# maplemini.net
KiCad netlist of a schematic drawn in EAGLE
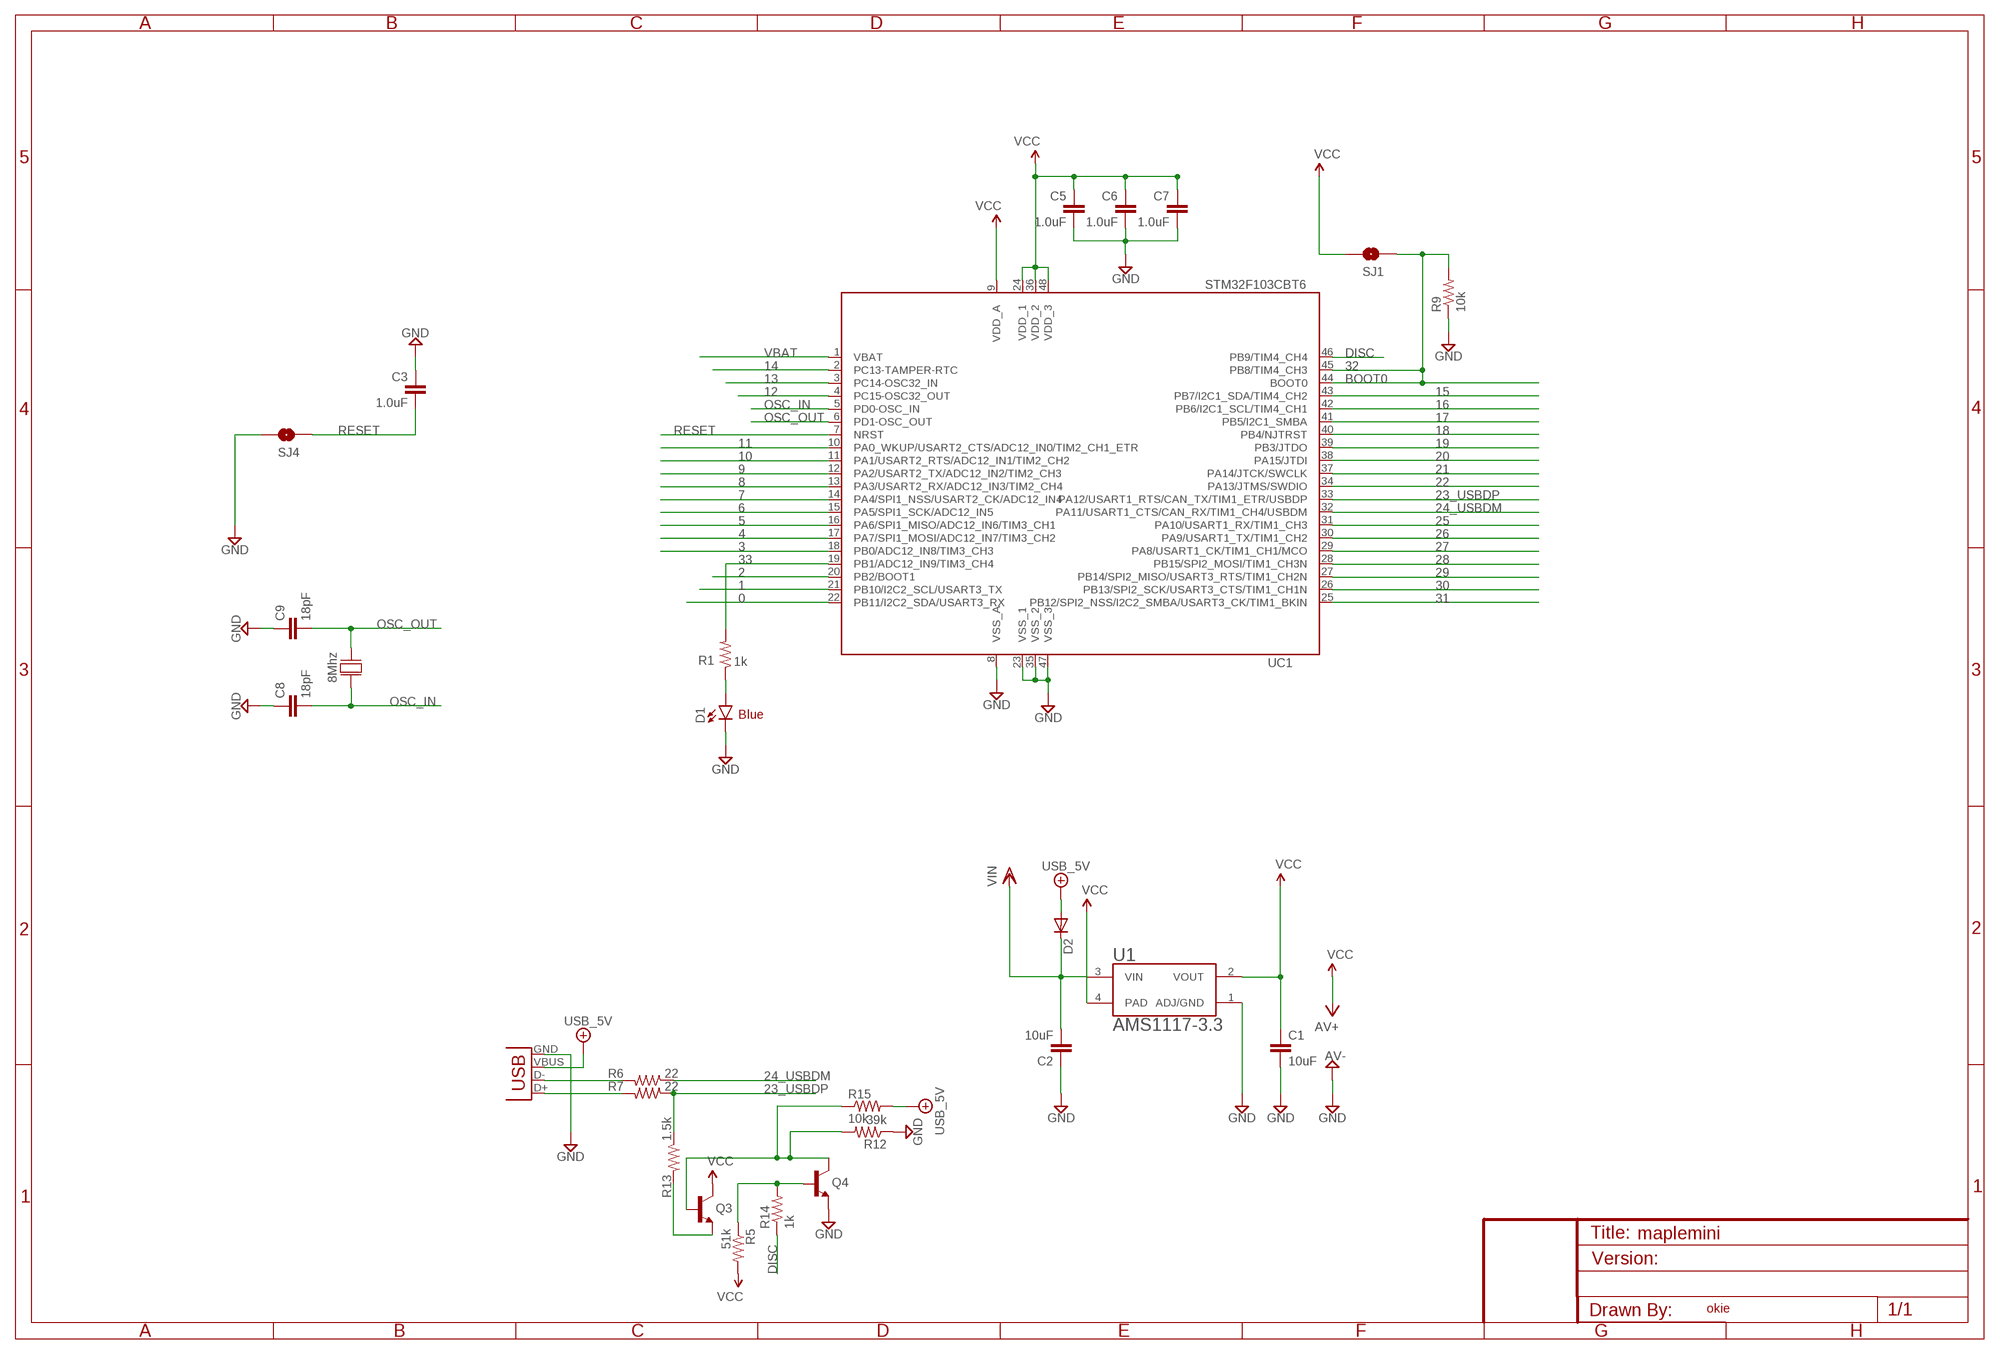
[diagram p0: schematic, sheet 1]

(export (version "E")
  (design (tool "Eeschema 10.0.6"))
  (components
    (comp (ref "C1")
      (value "10uF")
      (footprint "eagle-import:0805")
      (libsource (lib "eagle-import") (part "CAP0805"))
    )
    (comp (ref "C2")
      (value "10uF")
      (footprint "eagle-import:0805")
      (libsource (lib "eagle-import") (part "CAP0805"))
    )
    (comp (ref "C3")
      (value "1.0uF")
      (footprint "eagle-import:0603")
      (libsource (lib "eagle-import") (part "1.0UF-0603-16V-10%"))
    )
    (comp (ref "C5")
      (value "1.0uF")
      (footprint "eagle-import:0603")
      (libsource (lib "eagle-import") (part "1.0UF-0603-16V-10%"))
    )
    (comp (ref "C6")
      (value "1.0uF")
      (footprint "eagle-import:0603")
      (libsource (lib "eagle-import") (part "1.0UF-0603-16V-10%"))
    )
    (comp (ref "C7")
      (value "1.0uF")
      (footprint "eagle-import:0603")
      (libsource (lib "eagle-import") (part "1.0UF-0603-16V-10%"))
    )
    (comp (ref "C8")
      (value "18pF")
      (footprint "eagle-import:0603")
      (libsource (lib "eagle-import") (part "18PF-0603-50V-5%"))
    )
    (comp (ref "C9")
      (value "18pF")
      (footprint "eagle-import:0603")
      (libsource (lib "eagle-import") (part "18PF-0603-50V-5%"))
    )
    (comp (ref "D1")
      (value "Blue")
      (footprint "eagle-import:LED-0603")
      (libsource (lib "eagle-import") (part "LED0603"))
    )
    (comp (ref "D2")
      (value "DIODESOD")
      (footprint "eagle-import:SOD-323")
      (libsource (lib "eagle-import") (part "DIODESOD"))
    )
    (comp (ref "Q3")
      (value "NPN-BJT")
      (footprint "eagle-import:SOT23")
      (libsource (lib "eagle-import") (part "TRANSISTOR_NPNSOT23"))
    )
    (comp (ref "Q4")
      (value "NPN-BJT")
      (footprint "eagle-import:SOT23")
      (libsource (lib "eagle-import") (part "TRANSISTOR_NPNSOT23"))
    )
    (comp (ref "R1")
      (value "1k")
      (footprint "eagle-import:0603")
      (libsource (lib "eagle-import") (part "1KOHM-0603-1/10W-1%"))
    )
    (comp (ref "R5")
      (value "51k")
      (footprint "eagle-import:0603")
      (libsource (lib "eagle-import") (part "47KOHM-0603-1/10W-1%"))
    )
    (comp (ref "R6")
      (value "22")
      (footprint "eagle-import:0603")
      (libsource (lib "eagle-import") (part "22OHM-0603-1/10W-1%"))
    )
    (comp (ref "R7")
      (value "22")
      (footprint "eagle-import:0603")
      (libsource (lib "eagle-import") (part "22OHM-0603-1/10W-1%"))
    )
    (comp (ref "R9")
      (value "10k")
      (footprint "eagle-import:0603")
      (libsource (lib "eagle-import") (part "10KOHM-0603-1/10W-1%"))
    )
    (comp (ref "R12")
      (value "39k")
      (footprint "eagle-import:0603")
      (libsource (lib "eagle-import") (part "39KOHM-0603-1/10W-1%"))
    )
    (comp (ref "R13")
      (value "1.5k")
      (footprint "eagle-import:0603")
      (libsource (lib "eagle-import") (part "22OHM-0603-1/10W-1%"))
    )
    (comp (ref "R14")
      (value "1k")
      (footprint "eagle-import:0603")
      (libsource (lib "eagle-import") (part "1KOHM-0603-1/10W-1%"))
    )
    (comp (ref "R15")
      (value "10k")
      (footprint "eagle-import:0603")
      (libsource (lib "eagle-import") (part "10KOHM-0603-1/10W-1%"))
    )
    (comp (ref "SJ1")
      (value "SOLDERJUMPERNO")
      (footprint "eagle-import:SJ_2S-NO")
      (libsource (lib "eagle-import") (part "SOLDERJUMPERNO"))
    )
    (comp (ref "SJ4")
      (value "SOLDERJUMPERNO")
      (footprint "eagle-import:SJ_2S-NO")
      (libsource (lib "eagle-import") (part "SOLDERJUMPERNO"))
    )
    (comp (ref "U$2")
      (value "8MHZCRYSTAL")
      (footprint "eagle-import:8MHZCRYSTAL")
      (libsource (lib "eagle-import") (part "8MHZCRYSTAL"))
    )
    (comp (ref "U1")
      (value "AMS1117-3.3")
      (footprint "eagle-import:SOT229P700X180-4N")
      (fields (field (name "MF") "Advanced Monolithic Systems"))
      (libsource (lib "eagle-import") (part "AMS1117-3.3"))
    )
    (comp (ref "UC1")
      (value "STM32F103CBT6")
      (footprint "eagle-import:LQFP48")
      (libsource (lib "eagle-import") (part "STM32F103CB"))
    )
    (comp (ref "X1")
      (value "USB-MINIB")
      (footprint "eagle-import:USB-MINIB")
      (libsource (lib "eagle-import") (part "USBSMD"))
    )
  )
  (nets
    (net (code "1") (name "/0") (class "Default")
      (node (ref "UC1") (pin "22") (pinfunction "PB11/I2C2_SDA/USART3_RX_22") (pintype "input"))
    )
    (net (code "2") (name "/1") (class "Default")
      (node (ref "UC1") (pin "21") (pinfunction "PB10/I2C2_SCL/USART3_TX_21") (pintype "input"))
    )
    (net (code "3") (name "/2") (class "Default")
      (node (ref "UC1") (pin "20") (pinfunction "PB2/BOOT1_20") (pintype "bidirectional"))
    )
    (net (code "4") (name "/3") (class "Default")
      (node (ref "UC1") (pin "18") (pinfunction "PB0/ADC12_IN8/TIM3_CH3_18") (pintype "bidirectional"))
    )
    (net (code "5") (name "/4") (class "Default")
      (node (ref "UC1") (pin "17") (pinfunction "PA7/SPI1_MOSI/ADC12_IN7/TIM3_CH2_17") (pintype "bidirectional"))
    )
    (net (code "6") (name "/5") (class "Default")
      (node (ref "UC1") (pin "16") (pinfunction "PA6/SPI1_MISO/ADC12_IN6/TIM3_CH1_16") (pintype "bidirectional"))
    )
    (net (code "7") (name "/6") (class "Default")
      (node (ref "UC1") (pin "15") (pinfunction "PA5/SPI1_SCK/ADC12_IN5_15") (pintype "bidirectional"))
    )
    (net (code "8") (name "/7") (class "Default")
      (node (ref "UC1") (pin "14") (pinfunction "PA4/SPI1_NSS/USART2_CK/ADC12_IN4_14") (pintype "bidirectional"))
    )
    (net (code "9") (name "/8") (class "Default")
      (node (ref "UC1") (pin "13") (pinfunction "PA3/USART2_RX/ADC12_IN3/TIM2_CH4_13") (pintype "bidirectional"))
    )
    (net (code "10") (name "/9") (class "Default")
      (node (ref "UC1") (pin "12") (pinfunction "PA2/USART2_TX/ADC12_IN2/TIM2_CH3_12") (pintype "bidirectional"))
    )
    (net (code "11") (name "/10") (class "Default")
      (node (ref "UC1") (pin "11") (pinfunction "PA1/USART2_RTS/ADC12_IN1/TIM2_CH2_11") (pintype "bidirectional"))
    )
    (net (code "12") (name "/11") (class "Default")
      (node (ref "UC1") (pin "10") (pinfunction "PA0_WKUP/USART2_CTS/ADC12_IN0/TIM2_CH1_ETR_10") (pintype "bidirectional"))
    )
    (net (code "13") (name "/12") (class "Default")
      (node (ref "UC1") (pin "4") (pinfunction "PC15-OSC32_OUT_4") (pintype "input"))
    )
    (net (code "14") (name "/13") (class "Default")
      (node (ref "UC1") (pin "3") (pinfunction "PC14-OSC32_IN_3") (pintype "input"))
    )
    (net (code "15") (name "/14") (class "Default")
      (node (ref "UC1") (pin "2") (pinfunction "PC13-TAMPER-RTC_2") (pintype "input"))
    )
    (net (code "16") (name "/15") (class "Default")
      (node (ref "UC1") (pin "43") (pinfunction "PB7/I2C1_SDA/TIM4_CH2_43") (pintype "bidirectional"))
    )
    (net (code "17") (name "/16") (class "Default")
      (node (ref "UC1") (pin "42") (pinfunction "PB6/I2C1_SCL/TIM4_CH1_42") (pintype "input"))
    )
    (net (code "18") (name "/17") (class "Default")
      (node (ref "UC1") (pin "41") (pinfunction "PB5/I2C1_SMBA_41") (pintype "input"))
    )
    (net (code "19") (name "/18") (class "Default")
      (node (ref "UC1") (pin "40") (pinfunction "PB4/NJTRST_40") (pintype "bidirectional"))
    )
    (net (code "20") (name "/19") (class "Default")
      (node (ref "UC1") (pin "39") (pinfunction "PB3/JTDO_39") (pintype "bidirectional"))
    )
    (net (code "21") (name "/20") (class "Default")
      (node (ref "UC1") (pin "38") (pinfunction "PA15/JTDI_38") (pintype "bidirectional"))
    )
    (net (code "22") (name "/21") (class "Default")
      (node (ref "UC1") (pin "37") (pinfunction "PA14/JTCK/SWCLK_37") (pintype "bidirectional"))
    )
    (net (code "23") (name "/22") (class "Default")
      (node (ref "UC1") (pin "34") (pinfunction "PA13/JTMS/SWDIO_34") (pintype "bidirectional"))
    )
    (net (code "24") (name "/23_USBDP") (class "Default")
      (node (ref "R13") (pin "1") (pinfunction "1_1") (pintype "passive"))
      (node (ref "R7") (pin "1") (pinfunction "1_1") (pintype "passive"))
      (node (ref "UC1") (pin "33") (pinfunction "PA12/USART1_RTS/CAN_TX/TIM1_ETR/USBDP_33") (pintype "bidirectional"))
    )
    (net (code "25") (name "/24_USBDM") (class "Default")
      (node (ref "R6") (pin "1") (pinfunction "1_1") (pintype "passive"))
      (node (ref "UC1") (pin "32") (pinfunction "PA11/USART1_CTS/CAN_RX/TIM1_CH4/USBDM_32") (pintype "bidirectional"))
    )
    (net (code "26") (name "/25") (class "Default")
      (node (ref "UC1") (pin "31") (pinfunction "PA10/USART1_RX/TIM1_CH3_31") (pintype "bidirectional"))
    )
    (net (code "27") (name "/26") (class "Default")
      (node (ref "UC1") (pin "30") (pinfunction "PA9/USART1_TX/TIM1_CH2_30") (pintype "input"))
    )
    (net (code "28") (name "/27") (class "Default")
      (node (ref "UC1") (pin "29") (pinfunction "PA8/USART1_CK/TIM1_CH1/MCO_29") (pintype "bidirectional"))
    )
    (net (code "29") (name "/28") (class "Default")
      (node (ref "UC1") (pin "28") (pinfunction "PB15/SPI2_MOSI/TIM1_CH3N_28") (pintype "input"))
    )
    (net (code "30") (name "/29") (class "Default")
      (node (ref "UC1") (pin "27") (pinfunction "PB14/SPI2_MISO/USART3_RTS/TIM1_CH2N_27") (pintype "input"))
    )
    (net (code "31") (name "/30") (class "Default")
      (node (ref "UC1") (pin "26") (pinfunction "PB13/SPI2_SCK/USART3_CTS/TIM1_CH1N_26") (pintype "input"))
    )
    (net (code "32") (name "/31") (class "Default")
      (node (ref "UC1") (pin "25") (pinfunction "PB12/SPI2_NSS/I2C2_SMBA/USART3_CK/TIM1_BKIN_25") (pintype "input"))
    )
    (net (code "33") (name "/32") (class "Default")
      (node (ref "R9") (pin "2") (pinfunction "2_2") (pintype "passive"))
      (node (ref "SJ1") (pin "1") (pinfunction "1_1") (pintype "passive"))
      (node (ref "UC1") (pin "44") (pinfunction "BOOT0_44") (pintype "input"))
      (node (ref "UC1") (pin "45") (pinfunction "PB8/TIM4_CH3_45") (pintype "bidirectional"))
    )
    (net (code "34") (name "/33") (class "Default")
      (node (ref "R1") (pin "2") (pinfunction "2_2") (pintype "passive"))
      (node (ref "UC1") (pin "19") (pinfunction "PB1/ADC12_IN9/TIM3_CH4_19") (pintype "bidirectional"))
    )
    (net (code "35") (name "/DISC") (class "Default")
      (node (ref "R14") (pin "1") (pinfunction "1_1") (pintype "passive"))
      (node (ref "UC1") (pin "46") (pinfunction "PB9/TIM4_CH4_46") (pintype "input"))
    )
    (net (code "36") (name "/OSC_IN") (class "Default")
      (node (ref "C8") (pin "2") (pinfunction "2_2") (pintype "passive"))
      (node (ref "U$2") (pin "P$1") (pinfunction "P$1_P$1") (pintype "bidirectional"))
      (node (ref "UC1") (pin "5") (pinfunction "PD0-OSC_IN_5") (pintype "input"))
    )
    (net (code "37") (name "/OSC_OUT") (class "Default")
      (node (ref "C9") (pin "2") (pinfunction "2_2") (pintype "passive"))
      (node (ref "U$2") (pin "P$2") (pinfunction "P$2_P$2") (pintype "bidirectional"))
      (node (ref "UC1") (pin "6") (pinfunction "PD1-OSC_OUT_6") (pintype "input"))
    )
    (net (code "38") (name "/RESET") (class "Default")
      (node (ref "C3") (pin "2") (pinfunction "2_2") (pintype "passive"))
      (node (ref "SJ4") (pin "1") (pinfunction "1_1") (pintype "passive"))
      (node (ref "UC1") (pin "7") (pinfunction "NRST_7") (pintype "input"))
    )
    (net (code "39") (name "/VBAT") (class "Default")
      (node (ref "UC1") (pin "1") (pinfunction "VBAT_1") (pintype "power_in"))
    )
    (net (code "40") (name "AV+") (class "Default")
      (node (ref "C1") (pin "1") (pinfunction "1_1") (pintype "passive"))
      (node (ref "C5") (pin "1") (pinfunction "1_1") (pintype "passive"))
      (node (ref "C6") (pin "1") (pinfunction "1_1") (pintype "passive"))
      (node (ref "C7") (pin "1") (pinfunction "1_1") (pintype "passive"))
      (node (ref "Q3") (pin "3") (pinfunction "C_3") (pintype "passive"))
      (node (ref "R5") (pin "2") (pinfunction "2_2") (pintype "passive"))
      (node (ref "SJ1") (pin "2") (pinfunction "2_2") (pintype "passive"))
      (node (ref "U1") (pin "2") (pinfunction "VOUT_2") (pintype "output"))
      (node (ref "U1") (pin "4") (pinfunction "PAD_4") (pintype "output"))
      (node (ref "UC1") (pin "24") (pinfunction "VDD_1_24") (pintype "power_in"))
      (node (ref "UC1") (pin "36") (pinfunction "VDD_2_36") (pintype "power_in"))
      (node (ref "UC1") (pin "48") (pinfunction "VDD_3_48") (pintype "power_in"))
      (node (ref "UC1") (pin "9") (pinfunction "VDD_A_9") (pintype "power_in"))
    )
    (net (code "41") (name "AV-") (class "Default")
      (node (ref "C1") (pin "2") (pinfunction "2_2") (pintype "passive"))
      (node (ref "C2") (pin "1") (pinfunction "1_1") (pintype "passive"))
      (node (ref "C3") (pin "1") (pinfunction "1_1") (pintype "passive"))
      (node (ref "C5") (pin "2") (pinfunction "2_2") (pintype "passive"))
      (node (ref "C6") (pin "2") (pinfunction "2_2") (pintype "passive"))
      (node (ref "C7") (pin "2") (pinfunction "2_2") (pintype "passive"))
      (node (ref "C8") (pin "1") (pinfunction "1_1") (pintype "passive"))
      (node (ref "C9") (pin "1") (pinfunction "1_1") (pintype "passive"))
      (node (ref "D1") (pin "C") (pinfunction "C_C") (pintype "passive"))
      (node (ref "Q4") (pin "2") (pinfunction "E_2") (pintype "passive"))
      (node (ref "R12") (pin "1") (pinfunction "1_1") (pintype "passive"))
      (node (ref "R9") (pin "1") (pinfunction "1_1") (pintype "passive"))
      (node (ref "SJ4") (pin "2") (pinfunction "2_2") (pintype "passive"))
      (node (ref "U1") (pin "1") (pinfunction "ADJ/GND_1") (pintype "power_in"))
      (node (ref "UC1") (pin "23") (pinfunction "VSS_1_23") (pintype "power_in"))
      (node (ref "UC1") (pin "35") (pinfunction "VSS_2_35") (pintype "power_in"))
      (node (ref "UC1") (pin "47") (pinfunction "VSS_3_47") (pintype "power_in"))
      (node (ref "UC1") (pin "8") (pinfunction "VSS_A_8") (pintype "power_in"))
      (node (ref "X1") (pin "GND") (pinfunction "GND_GND") (pintype "bidirectional"))
    )
    (net (code "42") (name "Net-(D1-PadA)") (class "Default")
      (node (ref "D1") (pin "A") (pinfunction "A_A") (pintype "passive"))
      (node (ref "R1") (pin "1") (pinfunction "1_1") (pintype "passive"))
    )
    (net (code "43") (name "Net-(Q3-B)") (class "Default")
      (node (ref "Q3") (pin "1") (pinfunction "B_1") (pintype "passive"))
      (node (ref "Q4") (pin "3") (pinfunction "C_3") (pintype "passive"))
      (node (ref "R12") (pin "2") (pinfunction "2_2") (pintype "passive"))
      (node (ref "R15") (pin "1") (pinfunction "1_1") (pintype "passive"))
    )
    (net (code "44") (name "Net-(Q3-E)") (class "Default")
      (node (ref "Q3") (pin "2") (pinfunction "E_2") (pintype "passive"))
      (node (ref "R13") (pin "2") (pinfunction "2_2") (pintype "passive"))
    )
    (net (code "45") (name "Net-(Q4-B)") (class "Default")
      (node (ref "Q4") (pin "1") (pinfunction "B_1") (pintype "passive"))
      (node (ref "R14") (pin "2") (pinfunction "2_2") (pintype "passive"))
      (node (ref "R5") (pin "1") (pinfunction "1_1") (pintype "passive"))
    )
    (net (code "46") (name "Net-(R6-Pad2)") (class "Default")
      (node (ref "R6") (pin "2") (pinfunction "2_2") (pintype "passive"))
      (node (ref "X1") (pin "D-") (pinfunction "D-_D-") (pintype "bidirectional"))
    )
    (net (code "47") (name "Net-(R7-Pad2)") (class "Default")
      (node (ref "R7") (pin "2") (pinfunction "2_2") (pintype "passive"))
      (node (ref "X1") (pin "D+") (pinfunction "D+_D+") (pintype "bidirectional"))
    )
    (net (code "48") (name "USB_5V") (class "Default")
      (node (ref "D2") (pin "2") (pinfunction "A_2") (pintype "passive"))
      (node (ref "R15") (pin "2") (pinfunction "2_2") (pintype "passive"))
      (node (ref "X1") (pin "VBUS") (pinfunction "VBUS_VBUS") (pintype "bidirectional"))
    )
    (net (code "49") (name "VIN") (class "Default")
      (node (ref "C2") (pin "2") (pinfunction "2_2") (pintype "passive"))
      (node (ref "D2") (pin "1") (pinfunction "C_1") (pintype "passive"))
      (node (ref "U1") (pin "3") (pinfunction "VIN_3") (pintype "input"))
    )
  )
)
